# esp32_gpio_board_7f3a0bd8d1424bb1b772e89.net
KiCad netlist of a schematic drawn in EasyEDA Pro
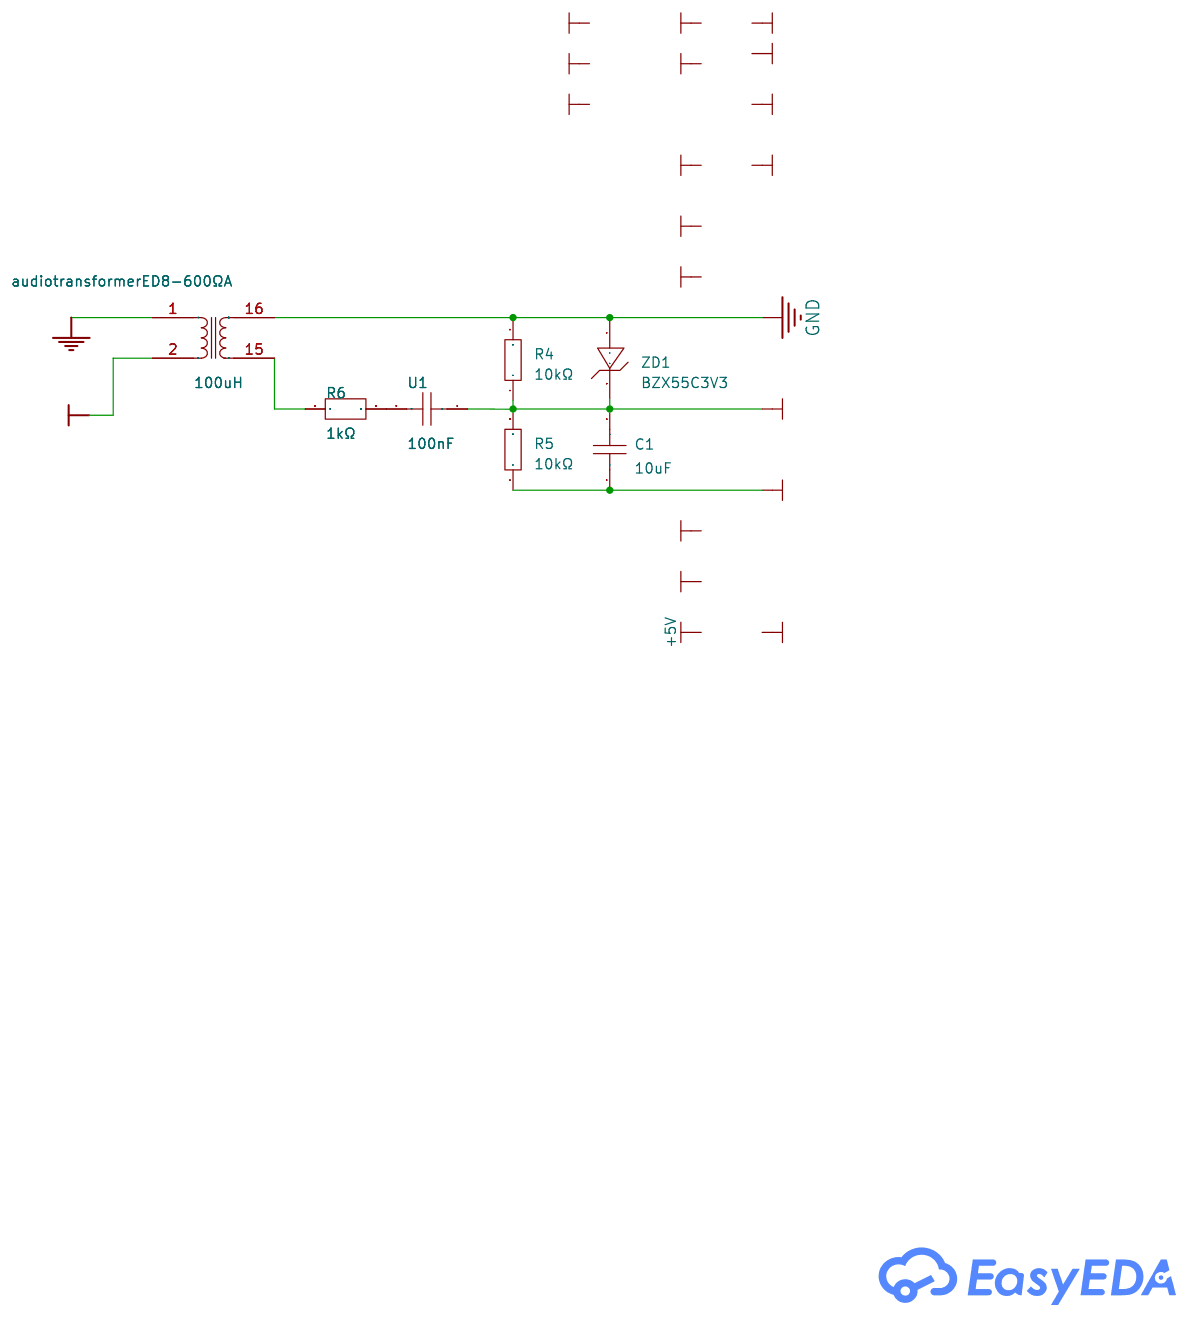
[diagram p0: schematic sheet]

(export (version "E")
  (design (tool "Eeschema 10.0.6"))
  (components
    (comp (ref "audiotransformerED8-600Ω")
      (value "100uH")
      (footprint "easyedapro:XFMR-SMD_16P-L12.8-W7.1-P1.27-LS9.5-BL")
      (fields (field (name "Manufacturer Part") "PE-65728NL") (field (name "Manufacturer") "PULSE(普思)"))
      (libsource (lib "easyedapro") (part "PE-65728NL"))
    )
    (comp (ref "C1")
      (value "10uF")
      (footprint "easyedapro:CAP-TH_L5.9-W4.2-P5.08-D0.5")
      (fields
        (field (name "Manufacturer Part") "CT4G-1210-X5R-50V-10uF-K")
        (field (name "Manufacturer") "TORCH(火炬)")
      )
      (libsource (lib "easyedapro") (part "CT4G-1210-X5R-50V-10μF-K"))
    )
    (comp (ref "R4")
      (value "10kΩ")
      (footprint "easyedapro:RES-TH_BD3.3-L9.0-P13.00-D0.6")
      (fields
        (field (name "Manufacturer Part") "RN1/2W10KΩFT/BA1")
        (field (name "Manufacturer") "Tyohm(幸亚电阻)")
      )
      (libsource (lib "easyedapro") (part "RN1/2W10KΩFT/BA1"))
    )
    (comp (ref "R5")
      (value "10kΩ")
      (footprint "easyedapro:RES-TH_BD3.3-L9.0-P13.00-D0.6")
      (fields
        (field (name "Manufacturer Part") "RN1/2W10KΩFT/BA1")
        (field (name "Manufacturer") "Tyohm(幸亚电阻)")
      )
      (libsource (lib "easyedapro") (part "RN1/2W10KΩFT/BA1"))
    )
    (comp (ref "R6")
      (value "1kΩ")
      (footprint "easyedapro:RES-TH_BD4.5-L11.5-P15.50-D0.7")
      (fields (field (name "Manufacturer Part") "MF2WS-1KΩ±1%T") (field (name "Manufacturer") "华星机电"))
      (libsource (lib "easyedapro") (part "MF2WS-1KΩ±1%T"))
    )
    (comp (ref "U1")
      (value "100nF")
      (footprint "easyedapro:CAP-TH_L5.0-W2.5-P5.00-D1.0")
      (libsource (lib "easyedapro") (part "100NF_C9900015256"))
    )
    (comp (ref "ZD1")
      (value "BZX55C3V3")
      (footprint "easyedapro:DO-35_BD2.0-L4.0-P8.00-D0.5-FD")
      (fields (field (name "Manufacturer") "ST(先科)"))
      (libsource (lib "easyedapro") (part "BZX55C3V3"))
    )
  )
  (nets
    (net (code "1") (name "+3.3V") (class "Default")
      (node (ref "C1") (pin "1") (pinfunction "1_1") (pintype "unspecified"))
      (node (ref "R5") (pin "1") (pinfunction "1_1") (pintype "unspecified"))
    )
    (net (code "3") (name "AUDIO_L") (class "Default")
      (node (ref "audiotransformerED8-600Ω") (pin "2") (pinfunction "2_2") (pintype "unspecified"))
    )
    (net (code "7") (name "GND") (class "Default")
      (node (ref "R4") (pin "2") (pinfunction "2_2") (pintype "unspecified"))
      (node (ref "ZD1") (pin "1") (pinfunction "A_1") (pintype "unspecified"))
      (node (ref "audiotransformerED8-600Ω") (pin "1") (pinfunction "1_1") (pintype "unspecified"))
      (node (ref "audiotransformerED8-600Ω") (pin "16") (pinfunction "16_16") (pintype "unspecified"))
    )
    (net (code "8") (name "GPIO_3") (class "Default")
      (node (ref "C1") (pin "2") (pinfunction "2_2") (pintype "unspecified"))
      (node (ref "R4") (pin "1") (pinfunction "1_1") (pintype "unspecified"))
      (node (ref "R5") (pin "2") (pinfunction "2_2") (pintype "unspecified"))
      (node (ref "U1") (pin "1") (pinfunction "1_1") (pintype "unspecified"))
      (node (ref "ZD1") (pin "2") (pinfunction "K_2") (pintype "unspecified"))
    )
    (net (code "14") (name "Net-(R6-Pad1)") (class "Default")
      (node (ref "R6") (pin "1") (pinfunction "1_1") (pintype "unspecified"))
      (node (ref "audiotransformerED8-600Ω") (pin "15") (pinfunction "15_15") (pintype "unspecified"))
    )
    (net (code "15") (name "Net-(R6-Pad2)") (class "Default")
      (node (ref "R6") (pin "2") (pinfunction "2_2") (pintype "unspecified"))
      (node (ref "U1") (pin "2") (pinfunction "2_2") (pintype "unspecified"))
    )
  )
)
